# basketball_main_board_2020-10-02_16-44-3.net
KiCad netlist of a schematic drawn in EasyEDA
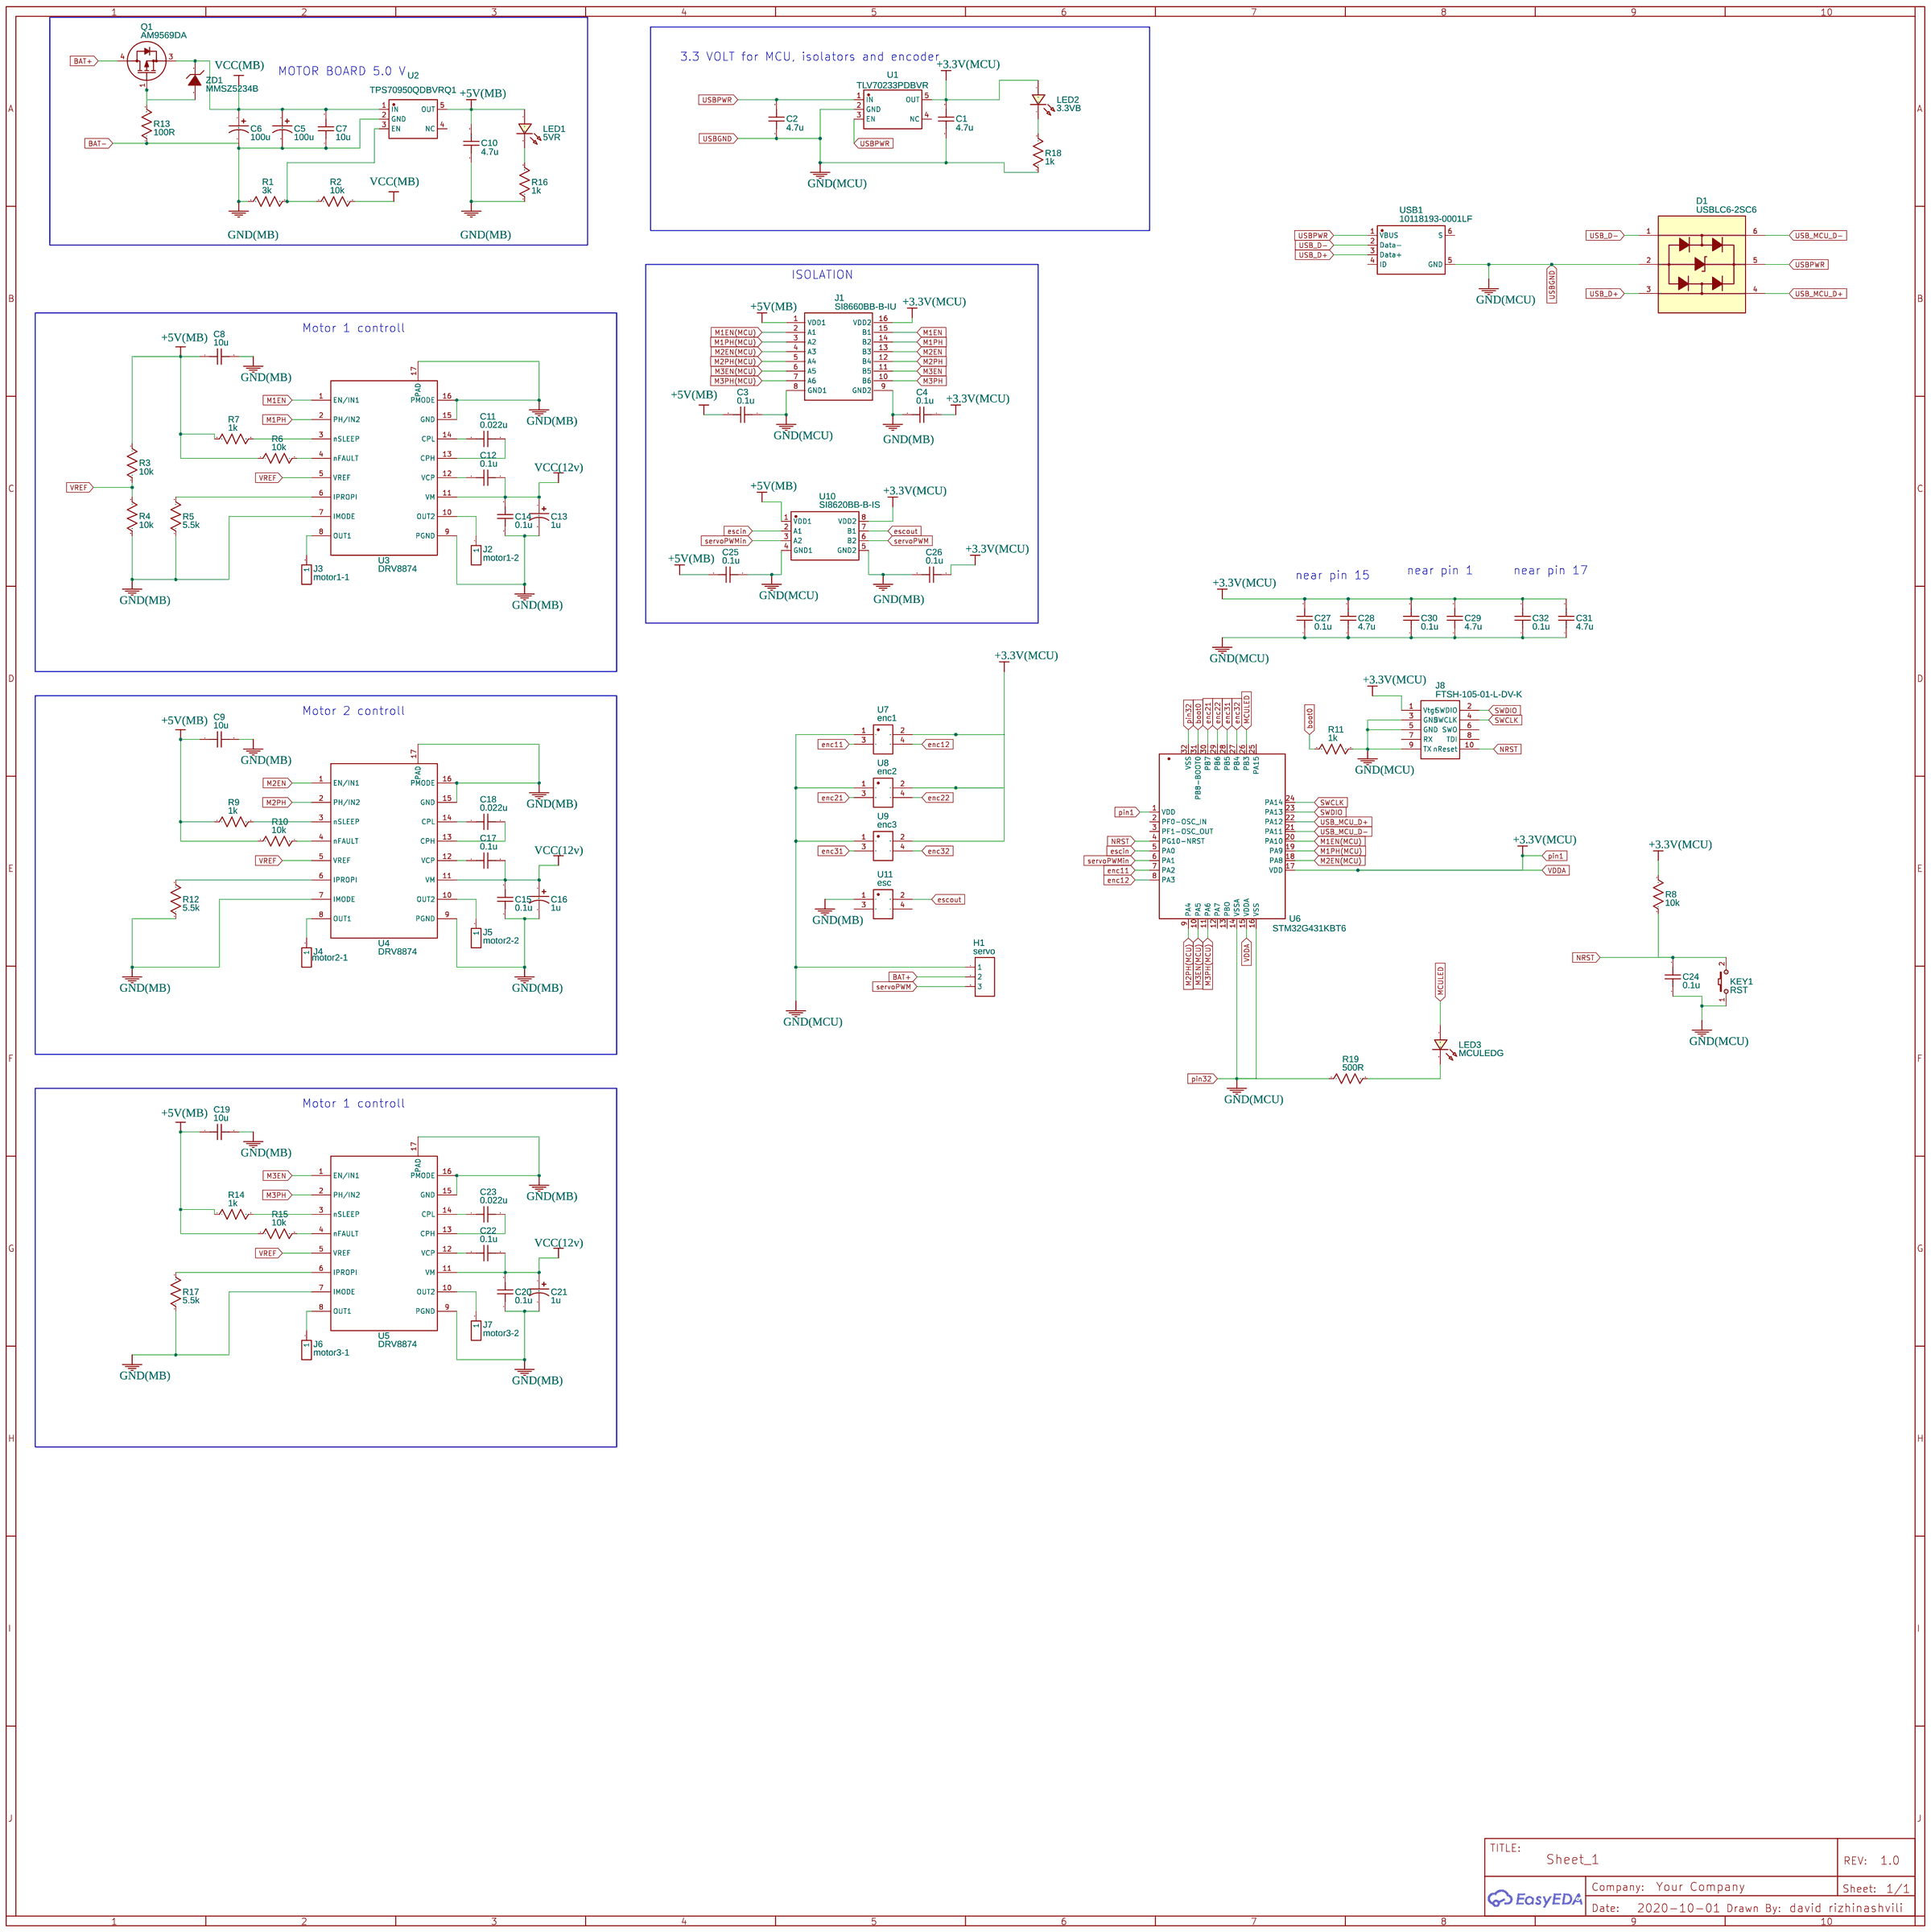
[diagram p0: schematic sheet]

(export (version "E")
  (design (tool "Eeschema 10.0.6"))
  (components
    (comp (ref "C1") (value "4.7u") (libsource (lib "") (part "C_1206_US")))
    (comp (ref "C2") (value "4.7u") (libsource (lib "") (part "C_1206_US")))
    (comp (ref "C3") (value "0.1u") (libsource (lib "") (part "C_1206_US_1")))
    (comp (ref "C4") (value "0.1u") (libsource (lib "") (part "C_1206_US_1")))
    (comp (ref "C5") (value "100u") (libsource (lib "") (part "CE_TH_D6.3×F2.5_US")))
    (comp (ref "C6") (value "100u") (libsource (lib "") (part "CE_TH_D6.3×F2.5_US_1")))
    (comp (ref "C7") (value "10u") (libsource (lib "") (part "C_1206_US")))
    (comp (ref "C8") (value "10u") (libsource (lib "") (part "C_1206_US_2")))
    (comp (ref "C9") (value "10u") (libsource (lib "") (part "C_1206_US_2")))
    (comp (ref "C10") (value "4.7u") (libsource (lib "") (part "C_1206_US")))
    (comp (ref "C11") (value "0.022u") (libsource (lib "") (part "C_1206_US_2")))
    (comp (ref "C12") (value "0.1u") (libsource (lib "") (part "C_1206_US_2")))
    (comp (ref "C13") (value "1u") (libsource (lib "") (part "CE_TH_D6.3×F2.5_US")))
    (comp (ref "C14") (value "0.1u") (libsource (lib "") (part "C_1206_US")))
    (comp (ref "C15") (value "0.1u") (libsource (lib "") (part "C_1206_US")))
    (comp (ref "C16") (value "1u") (libsource (lib "") (part "CE_TH_D6.3×F2.5_US_2")))
    (comp (ref "C17") (value "0.1u") (libsource (lib "") (part "C_1206_US_2")))
    (comp (ref "C18") (value "0.022u") (libsource (lib "") (part "C_1206_US_2")))
    (comp (ref "C19") (value "10u") (libsource (lib "") (part "C_1206_US_2")))
    (comp (ref "C20") (value "0.1u") (libsource (lib "") (part "C_1206_US")))
    (comp (ref "C21") (value "1u") (libsource (lib "") (part "CE_TH_D6.3×F2.5_US")))
    (comp (ref "C22") (value "0.1u") (libsource (lib "") (part "C_1206_US_2")))
    (comp (ref "C23") (value "0.022u") (libsource (lib "") (part "C_1206_US_2")))
    (comp (ref "C24") (value "0.1u") (libsource (lib "") (part "C_1206_US")))
    (comp (ref "C25") (value "0.1u") (libsource (lib "") (part "C_1206_US_1")))
    (comp (ref "C26") (value "0.1u") (libsource (lib "") (part "C_1206_US_1")))
    (comp (ref "C27") (value "0.1u") (libsource (lib "") (part "C_1206_US")))
    (comp (ref "C28") (value "4.7u") (libsource (lib "") (part "C_1206_US")))
    (comp (ref "C29") (value "4.7u") (libsource (lib "") (part "C_1206_US")))
    (comp (ref "C30") (value "0.1u") (libsource (lib "") (part "C_1206_US")))
    (comp (ref "C31") (value "4.7u") (libsource (lib "") (part "C_1206_US")))
    (comp (ref "C32") (value "0.1u") (libsource (lib "") (part "C_1206_US")))
    (comp (ref "D1")
      (value "USBLC6-2SC6")
      (fields (field (name "BOM_Supplier Part") "C7519"))
      (libsource (lib "") (part "USBLC6-2SC6"))
    )
    (comp (ref "H1")
      (value "servo")
      (fields (field (name "BOM_Supplier Part") "C146690"))
      (libsource (lib "") (part "HDR-F-2.54_1x3"))
    )
    (comp (ref "J1") (value "SI8660BB-B-IU") (libsource (lib "") (part "SI8660BB-B-IU")))
    (comp (ref "J2")
      (value "motor1-2")
      (fields (field (name "BOM_Supplier Part") "C81276"))
      (libsource (lib "") (part "HDR-M-2.54_1x1"))
    )
    (comp (ref "J3")
      (value "motor1-1")
      (fields (field (name "BOM_Supplier Part") "C81276"))
      (libsource (lib "") (part "HDR-M-2.54_1x1"))
    )
    (comp (ref "J4")
      (value "motor2-1")
      (fields (field (name "BOM_Supplier Part") "C81276"))
      (libsource (lib "") (part "HDR-M-2.54_1x1"))
    )
    (comp (ref "J5")
      (value "motor2-2")
      (fields (field (name "BOM_Supplier Part") "C81276"))
      (libsource (lib "") (part "HDR-M-2.54_1x1"))
    )
    (comp (ref "J6")
      (value "motor3-1")
      (fields (field (name "BOM_Supplier Part") "C81276"))
      (libsource (lib "") (part "HDR-M-2.54_1x1"))
    )
    (comp (ref "J7")
      (value "motor3-2")
      (fields (field (name "BOM_Supplier Part") "C81276"))
      (libsource (lib "") (part "HDR-M-2.54_1x1"))
    )
    (comp (ref "J8")
      (value "FTSH-105-01-L-DV-K")
      (fields (field (name "BOM_Supplier Part") "SAM8799-ND"))
      (libsource (lib "") (part "FTSH-105-01-L-DV-K"))
    )
    (comp (ref "KEY1")
      (value "RST")
      (fields
        (field (name "BOM_Manufacturer Part") "K2-1107ST-A4SW-06")
        (field (name "BOM_Supplier Part") "C118141")
      )
      (libsource (lib "") (part "K2-3.6×6.1_SMD"))
    )
    (comp (ref "LED1")
      (value "5VR")
      (fields
        (field (name "BOM_Manufacturer Part") "19-217/R6C-AL1M2VY/3T")
        (field (name "BOM_Supplier Part") "C72044")
      )
      (libsource (lib "") (part "LED-0603_R"))
    )
    (comp (ref "LED2")
      (value "3.3VB")
      (fields
        (field (name "BOM_Manufacturer Part") "19-217/R6C-AL1M2VY/3T")
        (field (name "BOM_Supplier Part") "C72044")
      )
      (libsource (lib "") (part "LED-0603_R"))
    )
    (comp (ref "LED3")
      (value "MCULEDG")
      (fields
        (field (name "BOM_Manufacturer Part") "19-217/R6C-AL1M2VY/3T")
        (field (name "BOM_Supplier Part") "C72044")
      )
      (libsource (lib "") (part "LED-0603_R"))
    )
    (comp (ref "Q1")
      (value "AM9569DA")
      (fields (field (name "BOM_Supplier Part") "C224223"))
      (libsource (lib "") (part "AM9569DA"))
    )
    (comp (ref "R1") (value "3k") (libsource (lib "") (part "R_1206_US_1")))
    (comp (ref "R2") (value "10k") (libsource (lib "") (part "R_1206_US_1")))
    (comp (ref "R3") (value "10k") (libsource (lib "") (part "R_0603_US_1")))
    (comp (ref "R4") (value "10k") (libsource (lib "") (part "R_0603_US_1")))
    (comp (ref "R5") (value "5.5k") (libsource (lib "") (part "R_0603_US_2")))
    (comp (ref "R6") (value "10k") (libsource (lib "") (part "R_0603_US")))
    (comp (ref "R7") (value "1k") (libsource (lib "") (part "R_0603_US")))
    (comp (ref "R8") (value "10k") (libsource (lib "") (part "R_1206_US")))
    (comp (ref "R9") (value "1k") (libsource (lib "") (part "R_0603_US")))
    (comp (ref "R10") (value "10k") (libsource (lib "") (part "R_0603_US")))
    (comp (ref "R11") (value "1k") (libsource (lib "") (part "R_1206_US_1")))
    (comp (ref "R12") (value "5.5k") (libsource (lib "") (part "R_0603_US_2")))
    (comp (ref "R13") (value "100R") (libsource (lib "") (part "R_1206_US")))
    (comp (ref "R14") (value "1k") (libsource (lib "") (part "R_0603_US")))
    (comp (ref "R15") (value "10k") (libsource (lib "") (part "R_0603_US")))
    (comp (ref "R16") (value "1k") (libsource (lib "") (part "R_1206_US")))
    (comp (ref "R17") (value "5.5k") (libsource (lib "") (part "R_0603_US_2")))
    (comp (ref "R18") (value "1k") (libsource (lib "") (part "R_1206_US")))
    (comp (ref "R19") (value "500R") (libsource (lib "") (part "R_1206_US_1")))
    (comp (ref "U1")
      (value "TLV70233PDBVR")
      (fields (field (name "BOM_Supplier Part") "C123134"))
      (libsource (lib "") (part "TLV70233PDBVR"))
    )
    (comp (ref "U2")
      (value "TPS70950QDBVRQ1")
      (fields (field (name "BOM_Supplier Part") "C485909"))
      (libsource (lib "") (part "TPS70950QDBVRQ1"))
    )
    (comp (ref "U3") (value "DRV8874") (libsource (lib "") (part "DRV8874")))
    (comp (ref "U4") (value "DRV8874") (libsource (lib "") (part "DRV8874")))
    (comp (ref "U5") (value "DRV8874") (libsource (lib "") (part "DRV8874")))
    (comp (ref "U6")
      (value "STM32G431KBT6")
      (fields (field (name "BOM_Supplier Part") "C529357"))
      (libsource (lib "") (part "STM32G431KBT6"))
    )
    (comp (ref "U7")
      (value "enc1")
      (fields (field (name "BOM_Manufacturer Part") "215079-4") (field (name "BOM_Supplier Part") "C306232"))
      (libsource (lib "") (part "215079-4"))
    )
    (comp (ref "U8")
      (value "enc2")
      (fields (field (name "BOM_Manufacturer Part") "215079-4") (field (name "BOM_Supplier Part") "C306232"))
      (libsource (lib "") (part "215079-4"))
    )
    (comp (ref "U9")
      (value "enc3")
      (fields (field (name "BOM_Manufacturer Part") "215079-4") (field (name "BOM_Supplier Part") "C306232"))
      (libsource (lib "") (part "215079-4"))
    )
    (comp (ref "U10")
      (value "SI8620BB-B-IS")
      (fields (field (name "BOM_Supplier Part") "C430264"))
      (libsource (lib "") (part "SI8620BB-B-IS"))
    )
    (comp (ref "U11")
      (value "esc")
      (fields (field (name "BOM_Manufacturer Part") "215079-4") (field (name "BOM_Supplier Part") "C306232"))
      (libsource (lib "") (part "215079-4"))
    )
    (comp (ref "USB1")
      (value "10118193-0001LF")
      (fields (field (name "BOM_Supplier Part") "C132562"))
      (libsource (lib "") (part "10118193-0001LF"))
    )
    (comp (ref "ZD1")
      (value "MMSZ5234B")
      (fields (field (name "BOM_Supplier Part") "C21556"))
      (libsource (lib "") (part "MMSZ5234B"))
    )
  )
  (nets
    (net (code "1") (name "+5V(MB)") (class "Default")
      (node (ref "C10") (pin "2") (pinfunction "2_2") (pintype "unspecified"))
      (node (ref "C19") (pin "1") (pinfunction "1_1") (pintype "unspecified"))
      (node (ref "C25") (pin "2") (pinfunction "2_2") (pintype "unspecified"))
      (node (ref "C3") (pin "2") (pinfunction "2_2") (pintype "unspecified"))
      (node (ref "C8") (pin "1") (pinfunction "1_1") (pintype "unspecified"))
      (node (ref "C9") (pin "1") (pinfunction "1_1") (pintype "unspecified"))
      (node (ref "J1") (pin "1") (pinfunction "VDD1_1") (pintype "bidirectional"))
      (node (ref "LED1") (pin "1") (pinfunction "1_1") (pintype "unspecified"))
      (node (ref "R10") (pin "1") (pinfunction "1_1") (pintype "unspecified"))
      (node (ref "R14") (pin "1") (pinfunction "1_1") (pintype "unspecified"))
      (node (ref "R15") (pin "1") (pinfunction "1_1") (pintype "unspecified"))
      (node (ref "R3") (pin "1") (pinfunction "1_1") (pintype "unspecified"))
      (node (ref "R6") (pin "1") (pinfunction "1_1") (pintype "unspecified"))
      (node (ref "R7") (pin "1") (pinfunction "1_1") (pintype "unspecified"))
      (node (ref "R9") (pin "1") (pinfunction "1_1") (pintype "unspecified"))
      (node (ref "U10") (pin "1") (pinfunction "VDD1_1") (pintype "unspecified"))
      (node (ref "U2") (pin "5") (pinfunction "OUT_5") (pintype "unspecified"))
    )
    (net (code "2") (name "BAT+") (class "Default")
      (node (ref "H1") (pin "2") (pinfunction "2_2") (pintype "input"))
      (node (ref "Q1") (pin "4") (pinfunction "D_4") (pintype "unspecified"))
    )
    (net (code "3") (name "BAT-") (class "Default")
      (node (ref "C10") (pin "1") (pinfunction "1_1") (pintype "unspecified"))
      (node (ref "C13") (pin "2") (pinfunction "2_2") (pintype "unspecified"))
      (node (ref "C14") (pin "1") (pinfunction "1_1") (pintype "unspecified"))
      (node (ref "C15") (pin "1") (pinfunction "1_1") (pintype "unspecified"))
      (node (ref "C16") (pin "2") (pinfunction "2_2") (pintype "unspecified"))
      (node (ref "C19") (pin "2") (pinfunction "2_2") (pintype "unspecified"))
      (node (ref "C20") (pin "1") (pinfunction "1_1") (pintype "unspecified"))
      (node (ref "C21") (pin "2") (pinfunction "2_2") (pintype "unspecified"))
      (node (ref "C26") (pin "2") (pinfunction "2_2") (pintype "unspecified"))
      (node (ref "C4") (pin "2") (pinfunction "2_2") (pintype "unspecified"))
      (node (ref "C5") (pin "2") (pinfunction "2_2") (pintype "unspecified"))
      (node (ref "C6") (pin "2") (pinfunction "2_2") (pintype "unspecified"))
      (node (ref "C7") (pin "1") (pinfunction "1_1") (pintype "unspecified"))
      (node (ref "C8") (pin "2") (pinfunction "2_2") (pintype "unspecified"))
      (node (ref "C9") (pin "2") (pinfunction "2_2") (pintype "unspecified"))
      (node (ref "J1") (pin "9") (pinfunction "GND2_9") (pintype "bidirectional"))
      (node (ref "R1") (pin "1") (pinfunction "1_1") (pintype "unspecified"))
      (node (ref "R12") (pin "1") (pinfunction "1_1") (pintype "unspecified"))
      (node (ref "R13") (pin "1") (pinfunction "1_1") (pintype "unspecified"))
      (node (ref "R16") (pin "1") (pinfunction "1_1") (pintype "unspecified"))
      (node (ref "R17") (pin "1") (pinfunction "1_1") (pintype "unspecified"))
      (node (ref "R4") (pin "2") (pinfunction "2_2") (pintype "unspecified"))
      (node (ref "R5") (pin "1") (pinfunction "1_1") (pintype "unspecified"))
      (node (ref "U10") (pin "5") (pinfunction "GND2_5") (pintype "unspecified"))
      (node (ref "U11") (pin "1") (pinfunction "1_1") (pintype "unspecified"))
      (node (ref "U2") (pin "2") (pinfunction "GND_2") (pintype "unspecified"))
      (node (ref "U3") (pin "15") (pinfunction "GND_15") (pintype "unspecified"))
      (node (ref "U3") (pin "16") (pinfunction "PMODE_16") (pintype "unspecified"))
      (node (ref "U3") (pin "17") (pinfunction "PAD_17") (pintype "unspecified"))
      (node (ref "U3") (pin "7") (pinfunction "IMODE_7") (pintype "unspecified"))
      (node (ref "U3") (pin "9") (pinfunction "PGND_9") (pintype "unspecified"))
      (node (ref "U4") (pin "15") (pinfunction "GND_15") (pintype "unspecified"))
      (node (ref "U4") (pin "16") (pinfunction "PMODE_16") (pintype "unspecified"))
      (node (ref "U4") (pin "17") (pinfunction "PAD_17") (pintype "unspecified"))
      (node (ref "U4") (pin "7") (pinfunction "IMODE_7") (pintype "unspecified"))
      (node (ref "U4") (pin "9") (pinfunction "PGND_9") (pintype "unspecified"))
      (node (ref "U5") (pin "15") (pinfunction "GND_15") (pintype "unspecified"))
      (node (ref "U5") (pin "16") (pinfunction "PMODE_16") (pintype "unspecified"))
      (node (ref "U5") (pin "17") (pinfunction "PAD_17") (pintype "unspecified"))
      (node (ref "U5") (pin "7") (pinfunction "IMODE_7") (pintype "unspecified"))
      (node (ref "U5") (pin "9") (pinfunction "PGND_9") (pintype "unspecified"))
    )
    (net (code "4") (name "M1EN") (class "Default")
      (node (ref "J1") (pin "15") (pinfunction "B1_15") (pintype "bidirectional"))
      (node (ref "U3") (pin "1") (pinfunction "EN/IN1_1") (pintype "unspecified"))
    )
    (net (code "5") (name "M1EN(MCU)") (class "Default")
      (node (ref "J1") (pin "2") (pinfunction "A1_2") (pintype "bidirectional"))
      (node (ref "U6") (pin "20") (pinfunction "PA10_20") (pintype "unspecified"))
    )
    (net (code "6") (name "M1PH") (class "Default")
      (node (ref "J1") (pin "14") (pinfunction "B2_14") (pintype "bidirectional"))
      (node (ref "U3") (pin "2") (pinfunction "PH/IN2_2") (pintype "unspecified"))
    )
    (net (code "7") (name "M1PH(MCU)") (class "Default")
      (node (ref "J1") (pin "3") (pinfunction "A2_3") (pintype "bidirectional"))
      (node (ref "U6") (pin "19") (pinfunction "PA9_19") (pintype "unspecified"))
    )
    (net (code "8") (name "M2EN") (class "Default")
      (node (ref "J1") (pin "13") (pinfunction "B3_13") (pintype "bidirectional"))
      (node (ref "U4") (pin "1") (pinfunction "EN/IN1_1") (pintype "unspecified"))
    )
    (net (code "9") (name "M2EN(MCU)") (class "Default")
      (node (ref "J1") (pin "4") (pinfunction "A3_4") (pintype "bidirectional"))
      (node (ref "U6") (pin "18") (pinfunction "PA8_18") (pintype "unspecified"))
    )
    (net (code "10") (name "M2PH") (class "Default")
      (node (ref "J1") (pin "12") (pinfunction "B4_12") (pintype "bidirectional"))
      (node (ref "U4") (pin "2") (pinfunction "PH/IN2_2") (pintype "unspecified"))
    )
    (net (code "11") (name "M2PH(MCU)") (class "Default")
      (node (ref "J1") (pin "5") (pinfunction "A4_5") (pintype "bidirectional"))
      (node (ref "U6") (pin "9") (pinfunction "PA4_9") (pintype "unspecified"))
    )
    (net (code "12") (name "M3EN") (class "Default")
      (node (ref "J1") (pin "11") (pinfunction "B5_11") (pintype "bidirectional"))
      (node (ref "U5") (pin "1") (pinfunction "EN/IN1_1") (pintype "unspecified"))
    )
    (net (code "13") (name "M3EN(MCU)") (class "Default")
      (node (ref "J1") (pin "6") (pinfunction "A5_6") (pintype "bidirectional"))
      (node (ref "U6") (pin "10") (pinfunction "PA5_10") (pintype "unspecified"))
    )
    (net (code "14") (name "M3PH") (class "Default")
      (node (ref "J1") (pin "10") (pinfunction "B6_10") (pintype "bidirectional"))
      (node (ref "U5") (pin "2") (pinfunction "PH/IN2_2") (pintype "unspecified"))
    )
    (net (code "15") (name "M3PH(MCU)") (class "Default")
      (node (ref "J1") (pin "7") (pinfunction "A6_7") (pintype "bidirectional"))
      (node (ref "U6") (pin "11") (pinfunction "PA6_11") (pintype "unspecified"))
    )
    (net (code "16") (name "MCULED") (class "Default")
      (node (ref "LED3") (pin "1") (pinfunction "1_1") (pintype "unspecified"))
      (node (ref "U6") (pin "26") (pinfunction "PB3_26") (pintype "unspecified"))
    )
    (net (code "17") (name "NRST") (class "Default")
      (node (ref "C24") (pin "2") (pinfunction "2_2") (pintype "unspecified"))
      (node (ref "J8") (pin "10") (pinfunction "nReset_10") (pintype "unspecified"))
      (node (ref "KEY1") (pin "2") (pinfunction "2_2") (pintype "unspecified"))
      (node (ref "R8") (pin "1") (pinfunction "1_1") (pintype "unspecified"))
      (node (ref "U6") (pin "4") (pinfunction "PG10-NRST_4") (pintype "unspecified"))
    )
    (net (code "18") (name "Net-(LED1-Pad2)") (class "Default")
      (node (ref "LED1") (pin "2") (pinfunction "2_2") (pintype "unspecified"))
      (node (ref "R16") (pin "2") (pinfunction "2_2") (pintype "unspecified"))
    )
    (net (code "19") (name "Net-(LED2-Pad2)") (class "Default")
      (node (ref "LED2") (pin "2") (pinfunction "2_2") (pintype "unspecified"))
      (node (ref "R18") (pin "2") (pinfunction "2_2") (pintype "unspecified"))
    )
    (net (code "20") (name "Net-(LED3-Pad2)") (class "Default")
      (node (ref "LED3") (pin "2") (pinfunction "2_2") (pintype "unspecified"))
      (node (ref "R19") (pin "2") (pinfunction "2_2") (pintype "unspecified"))
    )
    (net (code "21") (name "Net-(Q1-G)") (class "Default")
      (node (ref "Q1") (pin "1") (pinfunction "G_1") (pintype "unspecified"))
      (node (ref "R13") (pin "2") (pinfunction "2_2") (pintype "unspecified"))
      (node (ref "ZD1") (pin "2") (pinfunction "A_2") (pintype "unspecified"))
    )
    (net (code "22") (name "Net-(U2-EN)") (class "Default")
      (node (ref "R1") (pin "2") (pinfunction "2_2") (pintype "unspecified"))
      (node (ref "R2") (pin "1") (pinfunction "1_1") (pintype "unspecified"))
      (node (ref "U2") (pin "3") (pinfunction "EN_3") (pintype "unspecified"))
    )
    (net (code "23") (name "Net-(U3-CPH)") (class "Default")
      (node (ref "C11") (pin "2") (pinfunction "2_2") (pintype "unspecified"))
      (node (ref "U3") (pin "13") (pinfunction "CPH_13") (pintype "unspecified"))
    )
    (net (code "24") (name "Net-(U3-CPL)") (class "Default")
      (node (ref "C11") (pin "1") (pinfunction "1_1") (pintype "unspecified"))
      (node (ref "U3") (pin "14") (pinfunction "CPL_14") (pintype "unspecified"))
    )
    (net (code "25") (name "Net-(U3-IPROPI)") (class "Default")
      (node (ref "R5") (pin "2") (pinfunction "2_2") (pintype "unspecified"))
      (node (ref "U3") (pin "6") (pinfunction "IPROPI_6") (pintype "unspecified"))
    )
    (net (code "26") (name "Net-(U3-OUT1)") (class "Default")
      (node (ref "J3") (pin "1") (pinfunction "1_1") (pintype "input"))
      (node (ref "U3") (pin "8") (pinfunction "OUT1_8") (pintype "unspecified"))
    )
    (net (code "27") (name "Net-(U3-OUT2)") (class "Default")
      (node (ref "J2") (pin "1") (pinfunction "1_1") (pintype "input"))
      (node (ref "U3") (pin "10") (pinfunction "OUT2_10") (pintype "unspecified"))
    )
    (net (code "28") (name "Net-(U3-VCP)") (class "Default")
      (node (ref "C12") (pin "1") (pinfunction "1_1") (pintype "unspecified"))
      (node (ref "U3") (pin "12") (pinfunction "VCP_12") (pintype "unspecified"))
    )
    (net (code "29") (name "Net-(U3-nFAULT)") (class "Default")
      (node (ref "R6") (pin "2") (pinfunction "2_2") (pintype "unspecified"))
      (node (ref "U3") (pin "4") (pinfunction "nFAULT_4") (pintype "unspecified"))
    )
    (net (code "30") (name "Net-(U3-nSLEEP)") (class "Default")
      (node (ref "R7") (pin "2") (pinfunction "2_2") (pintype "unspecified"))
      (node (ref "U3") (pin "3") (pinfunction "nSLEEP_3") (pintype "unspecified"))
    )
    (net (code "31") (name "Net-(U4-CPH)") (class "Default")
      (node (ref "C18") (pin "2") (pinfunction "2_2") (pintype "unspecified"))
      (node (ref "U4") (pin "13") (pinfunction "CPH_13") (pintype "unspecified"))
    )
    (net (code "32") (name "Net-(U4-CPL)") (class "Default")
      (node (ref "C18") (pin "1") (pinfunction "1_1") (pintype "unspecified"))
      (node (ref "U4") (pin "14") (pinfunction "CPL_14") (pintype "unspecified"))
    )
    (net (code "33") (name "Net-(U4-IPROPI)") (class "Default")
      (node (ref "R12") (pin "2") (pinfunction "2_2") (pintype "unspecified"))
      (node (ref "U4") (pin "6") (pinfunction "IPROPI_6") (pintype "unspecified"))
    )
    (net (code "34") (name "Net-(U4-OUT1)") (class "Default")
      (node (ref "J4") (pin "1") (pinfunction "1_1") (pintype "input"))
      (node (ref "U4") (pin "8") (pinfunction "OUT1_8") (pintype "unspecified"))
    )
    (net (code "35") (name "Net-(U4-OUT2)") (class "Default")
      (node (ref "J5") (pin "1") (pinfunction "1_1") (pintype "input"))
      (node (ref "U4") (pin "10") (pinfunction "OUT2_10") (pintype "unspecified"))
    )
    (net (code "36") (name "Net-(U4-VCP)") (class "Default")
      (node (ref "C17") (pin "1") (pinfunction "1_1") (pintype "unspecified"))
      (node (ref "U4") (pin "12") (pinfunction "VCP_12") (pintype "unspecified"))
    )
    (net (code "37") (name "Net-(U4-nFAULT)") (class "Default")
      (node (ref "R10") (pin "2") (pinfunction "2_2") (pintype "unspecified"))
      (node (ref "U4") (pin "4") (pinfunction "nFAULT_4") (pintype "unspecified"))
    )
    (net (code "38") (name "Net-(U4-nSLEEP)") (class "Default")
      (node (ref "R9") (pin "2") (pinfunction "2_2") (pintype "unspecified"))
      (node (ref "U4") (pin "3") (pinfunction "nSLEEP_3") (pintype "unspecified"))
    )
    (net (code "39") (name "Net-(U5-CPH)") (class "Default")
      (node (ref "C23") (pin "2") (pinfunction "2_2") (pintype "unspecified"))
      (node (ref "U5") (pin "13") (pinfunction "CPH_13") (pintype "unspecified"))
    )
    (net (code "40") (name "Net-(U5-CPL)") (class "Default")
      (node (ref "C23") (pin "1") (pinfunction "1_1") (pintype "unspecified"))
      (node (ref "U5") (pin "14") (pinfunction "CPL_14") (pintype "unspecified"))
    )
    (net (code "41") (name "Net-(U5-IPROPI)") (class "Default")
      (node (ref "R17") (pin "2") (pinfunction "2_2") (pintype "unspecified"))
      (node (ref "U5") (pin "6") (pinfunction "IPROPI_6") (pintype "unspecified"))
    )
    (net (code "42") (name "Net-(U5-OUT1)") (class "Default")
      (node (ref "J6") (pin "1") (pinfunction "1_1") (pintype "input"))
      (node (ref "U5") (pin "8") (pinfunction "OUT1_8") (pintype "unspecified"))
    )
    (net (code "43") (name "Net-(U5-OUT2)") (class "Default")
      (node (ref "J7") (pin "1") (pinfunction "1_1") (pintype "input"))
      (node (ref "U5") (pin "10") (pinfunction "OUT2_10") (pintype "unspecified"))
    )
    (net (code "44") (name "Net-(U5-VCP)") (class "Default")
      (node (ref "C22") (pin "1") (pinfunction "1_1") (pintype "unspecified"))
      (node (ref "U5") (pin "12") (pinfunction "VCP_12") (pintype "unspecified"))
    )
    (net (code "45") (name "Net-(U5-nFAULT)") (class "Default")
      (node (ref "R15") (pin "2") (pinfunction "2_2") (pintype "unspecified"))
      (node (ref "U5") (pin "4") (pinfunction "nFAULT_4") (pintype "unspecified"))
    )
    (net (code "46") (name "Net-(U5-nSLEEP)") (class "Default")
      (node (ref "R14") (pin "2") (pinfunction "2_2") (pintype "unspecified"))
      (node (ref "U5") (pin "3") (pinfunction "nSLEEP_3") (pintype "unspecified"))
    )
    (net (code "47") (name "SWCLK") (class "Default")
      (node (ref "J8") (pin "4") (pinfunction "SWCLK_4") (pintype "unspecified"))
      (node (ref "U6") (pin "24") (pinfunction "PA14_24") (pintype "unspecified"))
    )
    (net (code "48") (name "SWDIO") (class "Default")
      (node (ref "J8") (pin "2") (pinfunction "SWDIO_2") (pintype "unspecified"))
      (node (ref "U6") (pin "23") (pinfunction "PA13_23") (pintype "unspecified"))
    )
    (net (code "49") (name "USBGND") (class "Default")
      (node (ref "C1") (pin "1") (pinfunction "1_1") (pintype "unspecified"))
      (node (ref "C2") (pin "1") (pinfunction "1_1") (pintype "unspecified"))
      (node (ref "C24") (pin "1") (pinfunction "1_1") (pintype "unspecified"))
      (node (ref "C25") (pin "1") (pinfunction "1_1") (pintype "unspecified"))
      (node (ref "C27") (pin "1") (pinfunction "1_1") (pintype "unspecified"))
      (node (ref "C28") (pin "1") (pinfunction "1_1") (pintype "unspecified"))
      (node (ref "C29") (pin "1") (pinfunction "1_1") (pintype "unspecified"))
      (node (ref "C3") (pin "1") (pinfunction "1_1") (pintype "unspecified"))
      (node (ref "C30") (pin "1") (pinfunction "1_1") (pintype "unspecified"))
      (node (ref "C31") (pin "1") (pinfunction "1_1") (pintype "unspecified"))
      (node (ref "C32") (pin "1") (pinfunction "1_1") (pintype "unspecified"))
      (node (ref "D1") (pin "2") (pinfunction "2_2") (pintype "input"))
      (node (ref "H1") (pin "1") (pinfunction "1_1") (pintype "input"))
      (node (ref "J1") (pin "8") (pinfunction "GND1_8") (pintype "bidirectional"))
      (node (ref "J8") (pin "3") (pinfunction "GND_3") (pintype "unspecified"))
      (node (ref "J8") (pin "5") (pinfunction "GND_5") (pintype "unspecified"))
      (node (ref "J8") (pin "9") (pinfunction "TX_9") (pintype "unspecified"))
      (node (ref "KEY1") (pin "1") (pinfunction "1_1") (pintype "unspecified"))
      (node (ref "R11") (pin "2") (pinfunction "2_2") (pintype "unspecified"))
      (node (ref "R18") (pin "1") (pinfunction "1_1") (pintype "unspecified"))
      (node (ref "R19") (pin "1") (pinfunction "1_1") (pintype "unspecified"))
      (node (ref "U1") (pin "2") (pinfunction "GND_2") (pintype "unspecified"))
      (node (ref "U10") (pin "4") (pinfunction "GND1_4") (pintype "unspecified"))
      (node (ref "U6") (pin "14") (pinfunction "VSSA_14") (pintype "unspecified"))
      (node (ref "U6") (pin "16") (pinfunction "VSS_16") (pintype "unspecified"))
      (node (ref "U6") (pin "32") (pinfunction "VSS_32") (pintype "unspecified"))
      (node (ref "U7") (pin "1") (pinfunction "1_1") (pintype "unspecified"))
      (node (ref "U8") (pin "1") (pinfunction "1_1") (pintype "unspecified"))
      (node (ref "U9") (pin "1") (pinfunction "1_1") (pintype "unspecified"))
      (node (ref "USB1") (pin "5") (pinfunction "GND_5") (pintype "unspecified"))
    )
    (net (code "50") (name "USBPWR") (class "Default")
      (node (ref "C2") (pin "2") (pinfunction "2_2") (pintype "unspecified"))
      (node (ref "D1") (pin "5") (pinfunction "5_5") (pintype "input"))
      (node (ref "U1") (pin "1") (pinfunction "IN_1") (pintype "unspecified"))
      (node (ref "U1") (pin "3") (pinfunction "EN_3") (pintype "unspecified"))
      (node (ref "USB1") (pin "1") (pinfunction "VBUS_1") (pintype "unspecified"))
    )
    (net (code "51") (name "USB_D+") (class "Default")
      (node (ref "D1") (pin "3") (pinfunction "3_3") (pintype "input"))
      (node (ref "USB1") (pin "3") (pinfunction "Data+_3") (pintype "unspecified"))
    )
    (net (code "52") (name "USB_D-") (class "Default")
      (node (ref "D1") (pin "1") (pinfunction "1_1") (pintype "input"))
      (node (ref "USB1") (pin "2") (pinfunction "Data-_2") (pintype "unspecified"))
    )
    (net (code "53") (name "USB_MCU_D+") (class "Default")
      (node (ref "D1") (pin "4") (pinfunction "4_4") (pintype "input"))
      (node (ref "U6") (pin "22") (pinfunction "PA12_22") (pintype "unspecified"))
    )
    (net (code "54") (name "USB_MCU_D-") (class "Default")
      (node (ref "D1") (pin "6") (pinfunction "6_6") (pintype "input"))
      (node (ref "U6") (pin "21") (pinfunction "PA11_21") (pintype "unspecified"))
    )
    (net (code "55") (name "VCC(12v)") (class "Default")
      (node (ref "C12") (pin "2") (pinfunction "2_2") (pintype "unspecified"))
      (node (ref "C13") (pin "1") (pinfunction "1_1") (pintype "unspecified"))
      (node (ref "C14") (pin "2") (pinfunction "2_2") (pintype "unspecified"))
      (node (ref "C15") (pin "2") (pinfunction "2_2") (pintype "unspecified"))
      (node (ref "C16") (pin "1") (pinfunction "1_1") (pintype "unspecified"))
      (node (ref "C17") (pin "2") (pinfunction "2_2") (pintype "unspecified"))
      (node (ref "C20") (pin "2") (pinfunction "2_2") (pintype "unspecified"))
      (node (ref "C21") (pin "1") (pinfunction "1_1") (pintype "unspecified"))
      (node (ref "C22") (pin "2") (pinfunction "2_2") (pintype "unspecified"))
      (node (ref "U3") (pin "11") (pinfunction "VM_11") (pintype "unspecified"))
      (node (ref "U4") (pin "11") (pinfunction "VM_11") (pintype "unspecified"))
      (node (ref "U5") (pin "11") (pinfunction "VM_11") (pintype "unspecified"))
    )
    (net (code "56") (name "VCC(MB)") (class "Default")
      (node (ref "C5") (pin "1") (pinfunction "1_1") (pintype "unspecified"))
      (node (ref "C6") (pin "1") (pinfunction "1_1") (pintype "unspecified"))
      (node (ref "C7") (pin "2") (pinfunction "2_2") (pintype "unspecified"))
      (node (ref "Q1") (pin "3") (pinfunction "S_3") (pintype "unspecified"))
      (node (ref "R2") (pin "2") (pinfunction "2_2") (pintype "unspecified"))
      (node (ref "U2") (pin "1") (pinfunction "IN_1") (pintype "unspecified"))
      (node (ref "ZD1") (pin "1") (pinfunction "K_1") (pintype "unspecified"))
    )
    (net (code "57") (name "VDDA") (class "Default")
      (node (ref "C1") (pin "2") (pinfunction "2_2") (pintype "unspecified"))
      (node (ref "C26") (pin "1") (pinfunction "1_1") (pintype "unspecified"))
      (node (ref "C27") (pin "2") (pinfunction "2_2") (pintype "unspecified"))
      (node (ref "C28") (pin "2") (pinfunction "2_2") (pintype "unspecified"))
      (node (ref "C29") (pin "2") (pinfunction "2_2") (pintype "unspecified"))
      (node (ref "C30") (pin "2") (pinfunction "2_2") (pintype "unspecified"))
      (node (ref "C31") (pin "2") (pinfunction "2_2") (pintype "unspecified"))
      (node (ref "C32") (pin "2") (pinfunction "2_2") (pintype "unspecified"))
      (node (ref "C4") (pin "1") (pinfunction "1_1") (pintype "unspecified"))
      (node (ref "J1") (pin "16") (pinfunction "VDD2_16") (pintype "bidirectional"))
      (node (ref "J8") (pin "1") (pinfunction "Vtgt_1") (pintype "unspecified"))
      (node (ref "LED2") (pin "1") (pinfunction "1_1") (pintype "unspecified"))
      (node (ref "R8") (pin "2") (pinfunction "2_2") (pintype "unspecified"))
      (node (ref "U1") (pin "5") (pinfunction "OUT_5") (pintype "unspecified"))
      (node (ref "U10") (pin "8") (pinfunction "VDD2_8") (pintype "unspecified"))
      (node (ref "U6") (pin "1") (pinfunction "VDD_1") (pintype "unspecified"))
      (node (ref "U6") (pin "15") (pinfunction "VDDA_15") (pintype "unspecified"))
      (node (ref "U6") (pin "17") (pinfunction "VDD_17") (pintype "unspecified"))
      (node (ref "U7") (pin "2") (pinfunction "2_2") (pintype "unspecified"))
      (node (ref "U8") (pin "2") (pinfunction "2_2") (pintype "unspecified"))
      (node (ref "U9") (pin "2") (pinfunction "2_2") (pintype "unspecified"))
    )
    (net (code "58") (name "VREF") (class "Default")
      (node (ref "R3") (pin "2") (pinfunction "2_2") (pintype "unspecified"))
      (node (ref "R4") (pin "1") (pinfunction "1_1") (pintype "unspecified"))
      (node (ref "U3") (pin "5") (pinfunction "VREF_5") (pintype "unspecified"))
      (node (ref "U4") (pin "5") (pinfunction "VREF_5") (pintype "unspecified"))
      (node (ref "U5") (pin "5") (pinfunction "VREF_5") (pintype "unspecified"))
    )
    (net (code "59") (name "boot0") (class "Default")
      (node (ref "R11") (pin "1") (pinfunction "1_1") (pintype "unspecified"))
      (node (ref "U6") (pin "31") (pinfunction "PB8-BOOT0_31") (pintype "unspecified"))
    )
    (net (code "60") (name "enc11") (class "Default")
      (node (ref "U6") (pin "7") (pinfunction "PA2_7") (pintype "unspecified"))
      (node (ref "U7") (pin "3") (pinfunction "3_3") (pintype "unspecified"))
    )
    (net (code "61") (name "enc12") (class "Default")
      (node (ref "U6") (pin "8") (pinfunction "PA3_8") (pintype "unspecified"))
      (node (ref "U7") (pin "4") (pinfunction "4_4") (pintype "unspecified"))
    )
    (net (code "62") (name "enc21") (class "Default")
      (node (ref "U6") (pin "30") (pinfunction "PB7_30") (pintype "unspecified"))
      (node (ref "U8") (pin "3") (pinfunction "3_3") (pintype "unspecified"))
    )
    (net (code "63") (name "enc22") (class "Default")
      (node (ref "U6") (pin "29") (pinfunction "PB6_29") (pintype "unspecified"))
      (node (ref "U8") (pin "4") (pinfunction "4_4") (pintype "unspecified"))
    )
    (net (code "64") (name "enc31") (class "Default")
      (node (ref "U6") (pin "28") (pinfunction "PB5_28") (pintype "unspecified"))
      (node (ref "U9") (pin "3") (pinfunction "3_3") (pintype "unspecified"))
    )
    (net (code "65") (name "enc32") (class "Default")
      (node (ref "U6") (pin "27") (pinfunction "PB4_27") (pintype "unspecified"))
      (node (ref "U9") (pin "4") (pinfunction "4_4") (pintype "unspecified"))
    )
    (net (code "66") (name "escin") (class "Default")
      (node (ref "U10") (pin "2") (pinfunction "A1_2") (pintype "unspecified"))
      (node (ref "U6") (pin "5") (pinfunction "PA0_5") (pintype "unspecified"))
    )
    (net (code "67") (name "escout") (class "Default")
      (node (ref "U10") (pin "7") (pinfunction "B1_7") (pintype "unspecified"))
      (node (ref "U11") (pin "2") (pinfunction "2_2") (pintype "unspecified"))
    )
    (net (code "68") (name "servoPWM") (class "Default")
      (node (ref "H1") (pin "3") (pinfunction "3_3") (pintype "input"))
      (node (ref "U10") (pin "6") (pinfunction "B2_6") (pintype "unspecified"))
    )
    (net (code "69") (name "servoPWMin") (class "Default")
      (node (ref "U10") (pin "3") (pinfunction "A2_3") (pintype "unspecified"))
      (node (ref "U6") (pin "6") (pinfunction "PA1_6") (pintype "unspecified"))
    )
    (net (code "70") (name "unconnected-(J8-RX-Pad7)") (class "Default")
      (node (ref "J8") (pin "7") (pinfunction "RX_7") (pintype "unspecified"))
    )
    (net (code "71") (name "unconnected-(J8-SWO-Pad6)") (class "Default")
      (node (ref "J8") (pin "6") (pinfunction "SWO_6") (pintype "unspecified"))
    )
    (net (code "72") (name "unconnected-(J8-TDI-Pad8)") (class "Default")
      (node (ref "J8") (pin "8") (pinfunction "TDI_8") (pintype "unspecified"))
    )
    (net (code "73") (name "unconnected-(U1-NC-Pad4)") (class "Default")
      (node (ref "U1") (pin "4") (pinfunction "NC_4") (pintype "unspecified"))
    )
    (net (code "74") (name "unconnected-(U2-NC-Pad4)") (class "Default")
      (node (ref "U2") (pin "4") (pinfunction "NC_4") (pintype "unspecified"))
    )
    (net (code "75") (name "unconnected-(U6-PA7-Pad12)") (class "Default")
      (node (ref "U6") (pin "12") (pinfunction "PA7_12") (pintype "unspecified"))
    )
    (net (code "76") (name "unconnected-(U6-PA15-Pad25)") (class "Default")
      (node (ref "U6") (pin "25") (pinfunction "PA15_25") (pintype "unspecified"))
    )
    (net (code "77") (name "unconnected-(U6-PBO-Pad13)") (class "Default")
      (node (ref "U6") (pin "13") (pinfunction "PBO_13") (pintype "unspecified"))
    )
    (net (code "78") (name "unconnected-(U6-PF0-OSC_IN-Pad2)") (class "Default")
      (node (ref "U6") (pin "2") (pinfunction "PF0-OSC_IN_2") (pintype "unspecified"))
    )
    (net (code "79") (name "unconnected-(U6-PF1-OSC_OUT-Pad3)") (class "Default")
      (node (ref "U6") (pin "3") (pinfunction "PF1-OSC_OUT_3") (pintype "unspecified"))
    )
    (net (code "80") (name "unconnected-(U11-Pad3)") (class "Default")
      (node (ref "U11") (pin "3") (pinfunction "3_3") (pintype "unspecified"))
    )
    (net (code "81") (name "unconnected-(U11-Pad4)") (class "Default")
      (node (ref "U11") (pin "4") (pinfunction "4_4") (pintype "unspecified"))
    )
    (net (code "82") (name "unconnected-(USB1-ID-Pad4)") (class "Default")
      (node (ref "USB1") (pin "4") (pinfunction "ID_4") (pintype "unspecified"))
    )
    (net (code "83") (name "unconnected-(USB1-S-Pad6)") (class "Default")
      (node (ref "USB1") (pin "6") (pinfunction "S_6") (pintype "unspecified"))
    )
  )
)
